# External_ADC.net
KiCad netlist of a schematic drawn in EAGLE
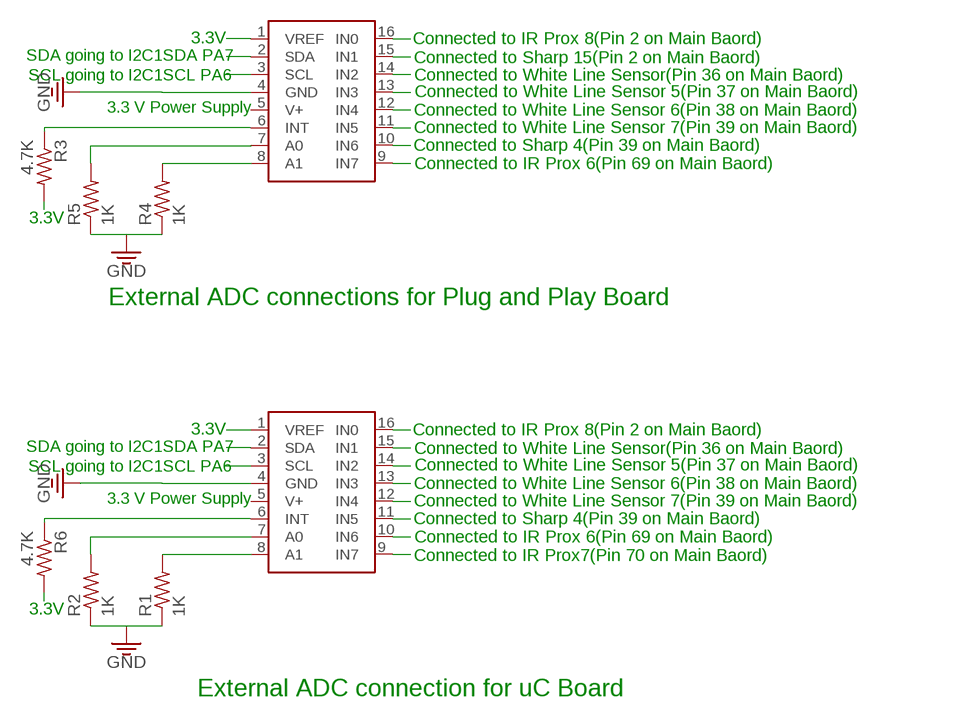
[diagram p0: schematic, sheet 1]

(export (version "E")
  (design (tool "Eeschema 10.0.6"))
  (components
    (comp (ref "R1")
      (value "1K")
      (footprint "eagle-import:M1206")
      (libsource (lib "eagle-import") (part "R-US_M1206"))
    )
    (comp (ref "R2")
      (value "1K")
      (footprint "eagle-import:M1206")
      (libsource (lib "eagle-import") (part "R-US_M1206"))
    )
    (comp (ref "R3")
      (value "4.7K")
      (footprint "eagle-import:M1206")
      (libsource (lib "eagle-import") (part "R-US_M1206"))
    )
    (comp (ref "R4")
      (value "1K")
      (footprint "eagle-import:M1206")
      (libsource (lib "eagle-import") (part "R-US_M1206"))
    )
    (comp (ref "R5")
      (value "1K")
      (footprint "eagle-import:M1206")
      (libsource (lib "eagle-import") (part "R-US_M1206"))
    )
    (comp (ref "R6")
      (value "4.7K")
      (footprint "eagle-import:M1206")
      (libsource (lib "eagle-import") (part "R-US_M1206"))
    )
    (comp (ref "U$1")
      (value "ADC128D818")
      (footprint "eagle-import:ADC12_SD")
      (libsource (lib "eagle-import") (part "ADC128D818"))
    )
    (comp (ref "U$4")
      (value "ADC128D818")
      (footprint "eagle-import:ADC12_SD")
      (libsource (lib "eagle-import") (part "ADC128D818"))
    )
  )
  (nets
    (net (code "2") (name "Net-(R1-Pad1)") (class "Default")
      (node (ref "R1") (pin "1") (pinfunction "1_1") (pintype "passive"))
      (node (ref "R2") (pin "1") (pinfunction "1_1") (pintype "passive"))
    )
    (net (code "3") (name "Net-(R4-Pad1)") (class "Default")
      (node (ref "R4") (pin "1") (pinfunction "1_1") (pintype "passive"))
      (node (ref "R5") (pin "1") (pinfunction "1_1") (pintype "passive"))
    )
    (net (code "4") (name "unconnected-(R1-Pad2)") (class "Default")
      (node (ref "R1") (pin "2") (pinfunction "2_2") (pintype "passive"))
    )
    (net (code "5") (name "unconnected-(R2-Pad2)") (class "Default")
      (node (ref "R2") (pin "2") (pinfunction "2_2") (pintype "passive"))
    )
    (net (code "6") (name "unconnected-(R3-Pad1)") (class "Default")
      (node (ref "R3") (pin "1") (pinfunction "1_1") (pintype "passive"))
    )
    (net (code "7") (name "unconnected-(R3-Pad2)") (class "Default")
      (node (ref "R3") (pin "2") (pinfunction "2_2") (pintype "passive"))
    )
    (net (code "8") (name "unconnected-(R4-Pad2)") (class "Default")
      (node (ref "R4") (pin "2") (pinfunction "2_2") (pintype "passive"))
    )
    (net (code "9") (name "unconnected-(R5-Pad2)") (class "Default")
      (node (ref "R5") (pin "2") (pinfunction "2_2") (pintype "passive"))
    )
    (net (code "10") (name "unconnected-(R6-Pad1)") (class "Default")
      (node (ref "R6") (pin "1") (pinfunction "1_1") (pintype "passive"))
    )
    (net (code "11") (name "unconnected-(R6-Pad2)") (class "Default")
      (node (ref "R6") (pin "2") (pinfunction "2_2") (pintype "passive"))
    )
    (net (code "12") (name "unconnected-(U$1-A0-Pad7)") (class "Default")
      (node (ref "U$1") (pin "7") (pinfunction "A0_7") (pintype "bidirectional"))
    )
    (net (code "13") (name "unconnected-(U$1-A1-Pad8)") (class "Default")
      (node (ref "U$1") (pin "8") (pinfunction "A1_8") (pintype "bidirectional"))
    )
    (net (code "14") (name "unconnected-(U$1-GND-Pad4)") (class "Default")
      (node (ref "U$1") (pin "4") (pinfunction "GND_4") (pintype "bidirectional"))
    )
    (net (code "15") (name "unconnected-(U$1-IN0-Pad16)") (class "Default")
      (node (ref "U$1") (pin "16") (pinfunction "IN0_16") (pintype "bidirectional"))
    )
    (net (code "16") (name "unconnected-(U$1-IN1-Pad15)") (class "Default")
      (node (ref "U$1") (pin "15") (pinfunction "IN1_15") (pintype "bidirectional"))
    )
    (net (code "17") (name "unconnected-(U$1-IN2-Pad14)") (class "Default")
      (node (ref "U$1") (pin "14") (pinfunction "IN2_14") (pintype "bidirectional"))
    )
    (net (code "18") (name "unconnected-(U$1-IN3-Pad13)") (class "Default")
      (node (ref "U$1") (pin "13") (pinfunction "IN3_13") (pintype "bidirectional"))
    )
    (net (code "19") (name "unconnected-(U$1-IN4-Pad12)") (class "Default")
      (node (ref "U$1") (pin "12") (pinfunction "IN4_12") (pintype "bidirectional"))
    )
    (net (code "20") (name "unconnected-(U$1-IN5-Pad11)") (class "Default")
      (node (ref "U$1") (pin "11") (pinfunction "IN5_11") (pintype "bidirectional"))
    )
    (net (code "21") (name "unconnected-(U$1-IN6-Pad10)") (class "Default")
      (node (ref "U$1") (pin "10") (pinfunction "IN6_10") (pintype "bidirectional"))
    )
    (net (code "22") (name "unconnected-(U$1-IN7-Pad9)") (class "Default")
      (node (ref "U$1") (pin "9") (pinfunction "IN7_9") (pintype "bidirectional"))
    )
    (net (code "23") (name "unconnected-(U$1-INT-Pad6)") (class "Default")
      (node (ref "U$1") (pin "6") (pinfunction "INT_6") (pintype "bidirectional"))
    )
    (net (code "24") (name "unconnected-(U$1-SCL-Pad3)") (class "Default")
      (node (ref "U$1") (pin "3") (pinfunction "SCL_3") (pintype "bidirectional"))
    )
    (net (code "25") (name "unconnected-(U$1-SDA-Pad2)") (class "Default")
      (node (ref "U$1") (pin "2") (pinfunction "SDA_2") (pintype "bidirectional"))
    )
    (net (code "26") (name "unconnected-(U$1-V+-Pad5)") (class "Default")
      (node (ref "U$1") (pin "5") (pinfunction "V+_5") (pintype "bidirectional"))
    )
    (net (code "27") (name "unconnected-(U$1-VREF-Pad1)") (class "Default")
      (node (ref "U$1") (pin "1") (pinfunction "VREF_1") (pintype "bidirectional"))
    )
    (net (code "28") (name "unconnected-(U$4-A0-Pad7)") (class "Default")
      (node (ref "U$4") (pin "7") (pinfunction "A0_7") (pintype "bidirectional"))
    )
    (net (code "29") (name "unconnected-(U$4-A1-Pad8)") (class "Default")
      (node (ref "U$4") (pin "8") (pinfunction "A1_8") (pintype "bidirectional"))
    )
    (net (code "30") (name "unconnected-(U$4-GND-Pad4)") (class "Default")
      (node (ref "U$4") (pin "4") (pinfunction "GND_4") (pintype "bidirectional"))
    )
    (net (code "31") (name "unconnected-(U$4-IN0-Pad16)") (class "Default")
      (node (ref "U$4") (pin "16") (pinfunction "IN0_16") (pintype "bidirectional"))
    )
    (net (code "32") (name "unconnected-(U$4-IN1-Pad15)") (class "Default")
      (node (ref "U$4") (pin "15") (pinfunction "IN1_15") (pintype "bidirectional"))
    )
    (net (code "33") (name "unconnected-(U$4-IN2-Pad14)") (class "Default")
      (node (ref "U$4") (pin "14") (pinfunction "IN2_14") (pintype "bidirectional"))
    )
    (net (code "34") (name "unconnected-(U$4-IN3-Pad13)") (class "Default")
      (node (ref "U$4") (pin "13") (pinfunction "IN3_13") (pintype "bidirectional"))
    )
    (net (code "35") (name "unconnected-(U$4-IN4-Pad12)") (class "Default")
      (node (ref "U$4") (pin "12") (pinfunction "IN4_12") (pintype "bidirectional"))
    )
    (net (code "36") (name "unconnected-(U$4-IN5-Pad11)") (class "Default")
      (node (ref "U$4") (pin "11") (pinfunction "IN5_11") (pintype "bidirectional"))
    )
    (net (code "37") (name "unconnected-(U$4-IN6-Pad10)") (class "Default")
      (node (ref "U$4") (pin "10") (pinfunction "IN6_10") (pintype "bidirectional"))
    )
    (net (code "38") (name "unconnected-(U$4-IN7-Pad9)") (class "Default")
      (node (ref "U$4") (pin "9") (pinfunction "IN7_9") (pintype "bidirectional"))
    )
    (net (code "39") (name "unconnected-(U$4-INT-Pad6)") (class "Default")
      (node (ref "U$4") (pin "6") (pinfunction "INT_6") (pintype "bidirectional"))
    )
    (net (code "40") (name "unconnected-(U$4-SCL-Pad3)") (class "Default")
      (node (ref "U$4") (pin "3") (pinfunction "SCL_3") (pintype "bidirectional"))
    )
    (net (code "41") (name "unconnected-(U$4-SDA-Pad2)") (class "Default")
      (node (ref "U$4") (pin "2") (pinfunction "SDA_2") (pintype "bidirectional"))
    )
    (net (code "42") (name "unconnected-(U$4-V+-Pad5)") (class "Default")
      (node (ref "U$4") (pin "5") (pinfunction "V+_5") (pintype "bidirectional"))
    )
    (net (code "43") (name "unconnected-(U$4-VREF-Pad1)") (class "Default")
      (node (ref "U$4") (pin "1") (pinfunction "VREF_1") (pintype "bidirectional"))
    )
  )
)
